# untitled.net
KiCad netlist of a schematic drawn in EAGLE
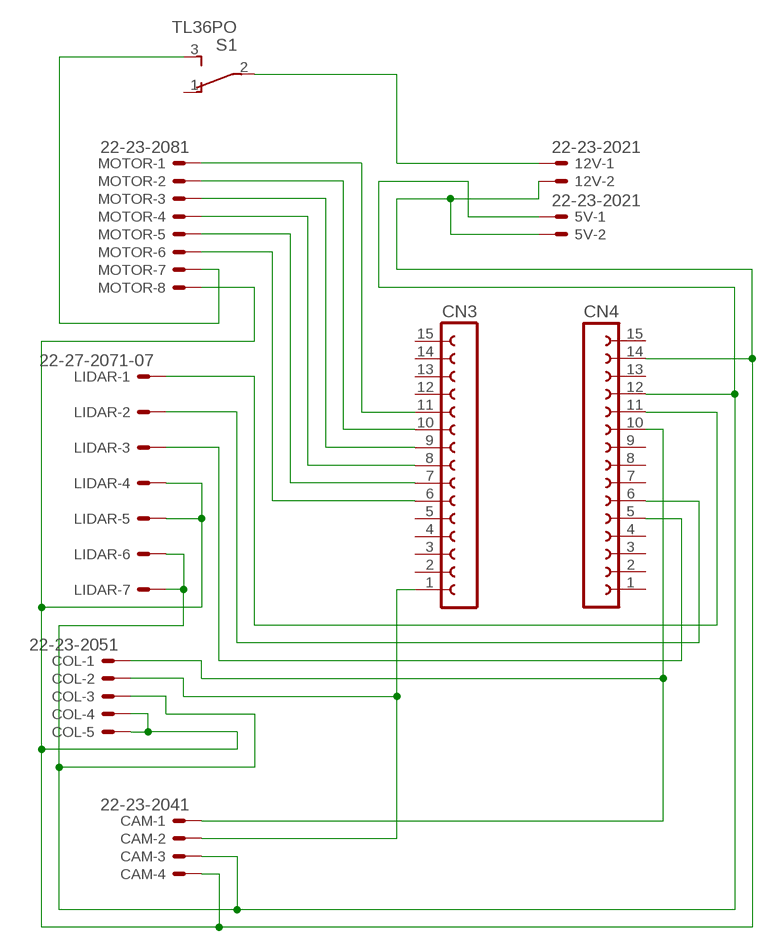
[diagram p0: schematic, sheet 1]

(export (version "E")
  (design (tool "Eeschema 10.0.6"))
  (components
    (comp (ref "5V")
      (value "22-23-2021")
      (footprint "eagle-import:22-23-2021")
      (fields (field (name "MF") "MOLEX"))
      (libsource (lib "eagle-import") (part "22-23-2021"))
    )
    (comp (ref "12V")
      (value "22-23-2021")
      (footprint "eagle-import:22-23-2021")
      (fields (field (name "MF") "MOLEX"))
      (libsource (lib "eagle-import") (part "22-23-2021"))
    )
    (comp (ref "CAM")
      (value "22-23-2041")
      (footprint "eagle-import:22-23-2041")
      (fields (field (name "MF") "MOLEX"))
      (libsource (lib "eagle-import") (part "22-23-2041"))
    )
    (comp (ref "CN3")
      (value "FE15-1")
      (footprint "eagle-import:FE15")
      (libsource (lib "eagle-import") (part "FE15-1"))
    )
    (comp (ref "CN4")
      (value "FE15-1")
      (footprint "eagle-import:FE15")
      (libsource (lib "eagle-import") (part "FE15-1"))
    )
    (comp (ref "COL")
      (value "22-23-2051")
      (footprint "eagle-import:22-23-2051")
      (fields (field (name "MF") "MOLEX"))
      (libsource (lib "eagle-import") (part "22-23-2051"))
    )
    (comp (ref "LIDAR")
      (value "22-27-2071-07")
      (footprint "eagle-import:6410-07")
      (fields (field (name "MF") "MOLEX"))
      (libsource (lib "eagle-import") (part "22-?-0727-2071"))
    )
    (comp (ref "MOTOR")
      (value "22-23-2081")
      (footprint "eagle-import:22-23-2081")
      (fields (field (name "MF") "MOLEX"))
      (libsource (lib "eagle-import") (part "22-23-2081"))
    )
    (comp (ref "S1")
      (value "TL36PO")
      (footprint "eagle-import:TL3XPO")
      (libsource (lib "eagle-import") (part "TL36PO"))
    )
  )
  (nets
    (net (code "1") (name "Net-(5VA-S)") (class "Default")
      (node (ref "5V") (pin "1") (pinfunction "S_1") (pintype "passive"))
      (node (ref "CAM") (pin "3") (pinfunction "S_3") (pintype "passive"))
      (node (ref "CN4") (pin "12") (pinfunction "12_12") (pintype "passive"))
      (node (ref "COL") (pin "3") (pinfunction "S_3") (pintype "passive"))
      (node (ref "LIDAR") (pin "6") (pinfunction "S_6") (pintype "passive"))
      (node (ref "LIDAR") (pin "7") (pinfunction "S_7") (pintype "passive"))
    )
    (net (code "2") (name "Net-(12VA-S)") (class "Default")
      (node (ref "12V") (pin "1") (pinfunction "S_1") (pintype "passive"))
      (node (ref "S1") (pin "2") (pinfunction "P_2") (pintype "passive"))
    )
    (net (code "3") (name "Net-(12VB-S)") (class "Default")
      (node (ref "12V") (pin "2") (pinfunction "S_2") (pintype "passive"))
      (node (ref "5V") (pin "2") (pinfunction "S_2") (pintype "passive"))
      (node (ref "CAM") (pin "4") (pinfunction "S_4") (pintype "passive"))
      (node (ref "CN4") (pin "14") (pinfunction "14_14") (pintype "passive"))
      (node (ref "COL") (pin "4") (pinfunction "S_4") (pintype "passive"))
      (node (ref "COL") (pin "5") (pinfunction "S_5") (pintype "passive"))
      (node (ref "LIDAR") (pin "4") (pinfunction "S_4") (pintype "passive"))
      (node (ref "LIDAR") (pin "5") (pinfunction "S_5") (pintype "passive"))
      (node (ref "MOTOR") (pin "8") (pinfunction "S_8") (pintype "passive"))
    )
    (net (code "4") (name "Net-(CAMA-S)") (class "Default")
      (node (ref "CAM") (pin "1") (pinfunction "S_1") (pintype "passive"))
      (node (ref "CN4") (pin "10") (pinfunction "10_10") (pintype "passive"))
      (node (ref "COL") (pin "1") (pinfunction "S_1") (pintype "passive"))
    )
    (net (code "5") (name "Net-(CAMB-S)") (class "Default")
      (node (ref "CAM") (pin "2") (pinfunction "S_2") (pintype "passive"))
      (node (ref "CN3") (pin "1") (pinfunction "1_1") (pintype "passive"))
      (node (ref "COL") (pin "2") (pinfunction "S_2") (pintype "passive"))
    )
    (net (code "6") (name "Net-(LIDARA-S)") (class "Default")
      (node (ref "CN4") (pin "11") (pinfunction "11_11") (pintype "passive"))
      (node (ref "LIDAR") (pin "1") (pinfunction "S_1") (pintype "passive"))
    )
    (net (code "7") (name "Net-(LIDARB-S)") (class "Default")
      (node (ref "CN4") (pin "6") (pinfunction "6_6") (pintype "passive"))
      (node (ref "LIDAR") (pin "2") (pinfunction "S_2") (pintype "passive"))
    )
    (net (code "8") (name "Net-(LIDARC-S)") (class "Default")
      (node (ref "CN4") (pin "5") (pinfunction "5_5") (pintype "passive"))
      (node (ref "LIDAR") (pin "3") (pinfunction "S_3") (pintype "passive"))
    )
    (net (code "9") (name "Net-(MOTORA-S)") (class "Default")
      (node (ref "CN3") (pin "11") (pinfunction "11_11") (pintype "passive"))
      (node (ref "MOTOR") (pin "1") (pinfunction "S_1") (pintype "passive"))
    )
    (net (code "10") (name "Net-(MOTORB-S)") (class "Default")
      (node (ref "CN3") (pin "10") (pinfunction "10_10") (pintype "passive"))
      (node (ref "MOTOR") (pin "2") (pinfunction "S_2") (pintype "passive"))
    )
    (net (code "11") (name "Net-(MOTORC-S)") (class "Default")
      (node (ref "CN3") (pin "9") (pinfunction "9_9") (pintype "passive"))
      (node (ref "MOTOR") (pin "3") (pinfunction "S_3") (pintype "passive"))
    )
    (net (code "12") (name "Net-(MOTORD-S)") (class "Default")
      (node (ref "CN3") (pin "8") (pinfunction "8_8") (pintype "passive"))
      (node (ref "MOTOR") (pin "4") (pinfunction "S_4") (pintype "passive"))
    )
    (net (code "13") (name "Net-(MOTORE-S)") (class "Default")
      (node (ref "CN3") (pin "7") (pinfunction "7_7") (pintype "passive"))
      (node (ref "MOTOR") (pin "5") (pinfunction "S_5") (pintype "passive"))
    )
    (net (code "14") (name "Net-(MOTORF-S)") (class "Default")
      (node (ref "CN3") (pin "6") (pinfunction "6_6") (pintype "passive"))
      (node (ref "MOTOR") (pin "6") (pinfunction "S_6") (pintype "passive"))
    )
    (net (code "15") (name "Net-(MOTORG-S)") (class "Default")
      (node (ref "MOTOR") (pin "7") (pinfunction "S_7") (pintype "passive"))
      (node (ref "S1") (pin "3") (pinfunction "S_3") (pintype "passive"))
    )
    (net (code "16") (name "unconnected-(CN3-Pad2)") (class "Default")
      (node (ref "CN3") (pin "2") (pinfunction "2_2") (pintype "passive"))
    )
    (net (code "17") (name "unconnected-(CN3-Pad3)") (class "Default")
      (node (ref "CN3") (pin "3") (pinfunction "3_3") (pintype "passive"))
    )
    (net (code "18") (name "unconnected-(CN3-Pad4)") (class "Default")
      (node (ref "CN3") (pin "4") (pinfunction "4_4") (pintype "passive"))
    )
    (net (code "19") (name "unconnected-(CN3-Pad5)") (class "Default")
      (node (ref "CN3") (pin "5") (pinfunction "5_5") (pintype "passive"))
    )
    (net (code "20") (name "unconnected-(CN3-Pad12)") (class "Default")
      (node (ref "CN3") (pin "12") (pinfunction "12_12") (pintype "passive"))
    )
    (net (code "21") (name "unconnected-(CN3-Pad13)") (class "Default")
      (node (ref "CN3") (pin "13") (pinfunction "13_13") (pintype "passive"))
    )
    (net (code "22") (name "unconnected-(CN3-Pad14)") (class "Default")
      (node (ref "CN3") (pin "14") (pinfunction "14_14") (pintype "passive"))
    )
    (net (code "23") (name "unconnected-(CN3-Pad15)") (class "Default")
      (node (ref "CN3") (pin "15") (pinfunction "15_15") (pintype "passive"))
    )
    (net (code "24") (name "unconnected-(CN4-Pad1)") (class "Default")
      (node (ref "CN4") (pin "1") (pinfunction "1_1") (pintype "passive"))
    )
    (net (code "25") (name "unconnected-(CN4-Pad2)") (class "Default")
      (node (ref "CN4") (pin "2") (pinfunction "2_2") (pintype "passive"))
    )
    (net (code "26") (name "unconnected-(CN4-Pad3)") (class "Default")
      (node (ref "CN4") (pin "3") (pinfunction "3_3") (pintype "passive"))
    )
    (net (code "27") (name "unconnected-(CN4-Pad4)") (class "Default")
      (node (ref "CN4") (pin "4") (pinfunction "4_4") (pintype "passive"))
    )
    (net (code "28") (name "unconnected-(CN4-Pad7)") (class "Default")
      (node (ref "CN4") (pin "7") (pinfunction "7_7") (pintype "passive"))
    )
    (net (code "29") (name "unconnected-(CN4-Pad8)") (class "Default")
      (node (ref "CN4") (pin "8") (pinfunction "8_8") (pintype "passive"))
    )
    (net (code "30") (name "unconnected-(CN4-Pad9)") (class "Default")
      (node (ref "CN4") (pin "9") (pinfunction "9_9") (pintype "passive"))
    )
    (net (code "31") (name "unconnected-(CN4-Pad13)") (class "Default")
      (node (ref "CN4") (pin "13") (pinfunction "13_13") (pintype "passive"))
    )
    (net (code "32") (name "unconnected-(CN4-Pad15)") (class "Default")
      (node (ref "CN4") (pin "15") (pinfunction "15_15") (pintype "passive"))
    )
    (net (code "33") (name "unconnected-(S1-O-Pad1)") (class "Default")
      (node (ref "S1") (pin "1") (pinfunction "O_1") (pintype "passive"))
    )
  )
)
